# Qwiic_1Wire_to_I2C_Bridge_DS28E17_MILLAB.net
KiCad netlist of a schematic drawn in EAGLE
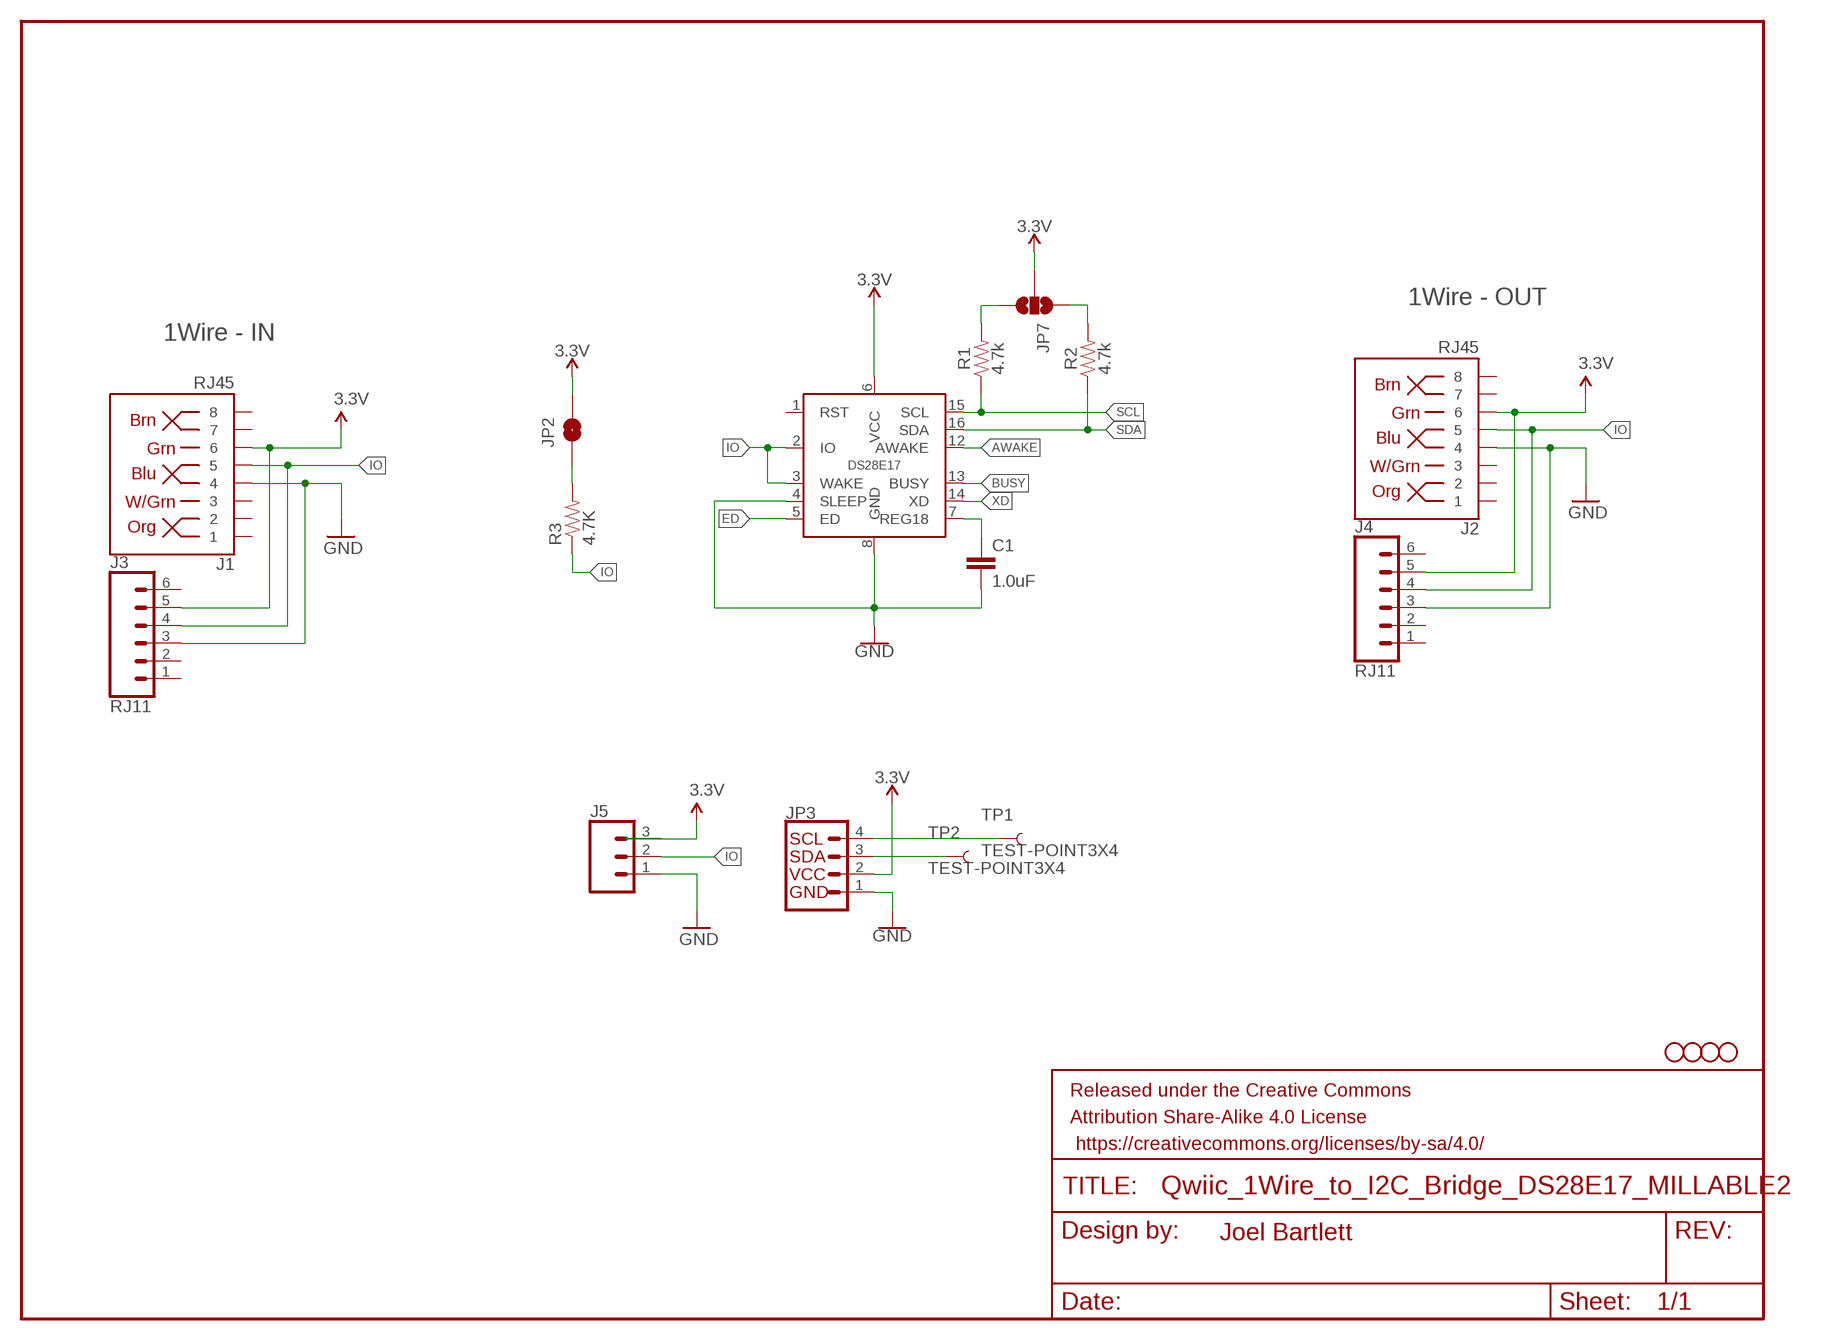
[diagram p0: schematic, sheet 1]

(export (version "E")
  (design (tool "Eeschema 10.0.6"))
  (components
    (comp (ref "C1")
      (value "1.0uF")
      (footprint "eagle-import:0603")
      (libsource (lib "eagle-import") (part "1.0UF-0603-16V-10%"))
    )
    (comp (ref "FRAME1")
      (value "FRAME-LETTER")
      (footprint "eagle-import:CREATIVE_COMMONS")
      (libsource (lib "eagle-import") (part "FRAME-LETTER"))
    )
    (comp (ref "H1")
      (value "STAND-OFF")
      (footprint "eagle-import:STAND-OFF")
      (libsource (lib "eagle-import") (part "STAND-OFF"))
    )
    (comp (ref "H2")
      (value "STAND-OFF")
      (footprint "eagle-import:STAND-OFF")
      (libsource (lib "eagle-import") (part "STAND-OFF"))
    )
    (comp (ref "H3")
      (value "STAND-OFF")
      (footprint "eagle-import:STAND-OFF")
      (libsource (lib "eagle-import") (part "STAND-OFF"))
    )
    (comp (ref "H4")
      (value "STAND-OFF")
      (footprint "eagle-import:STAND-OFF")
      (libsource (lib "eagle-import") (part "STAND-OFF"))
    )
    (comp (ref "J1")
      (value "RJ45")
      (footprint "eagle-import:RJ45-8")
      (libsource (lib "eagle-import") (part "RJ45-8"))
    )
    (comp (ref "J2")
      (value "RJ45")
      (footprint "eagle-import:RJ45-8")
      (libsource (lib "eagle-import") (part "RJ45-8"))
    )
    (comp (ref "J3")
      (value "RJ11")
      (footprint "eagle-import:RJ11-6")
      (libsource (lib "eagle-import") (part "RJ11-6"))
    )
    (comp (ref "J4")
      (value "RJ11")
      (footprint "eagle-import:RJ11-6")
      (libsource (lib "eagle-import") (part "RJ11-6"))
    )
    (comp (ref "J5")
      (value "CONN_03")
      (footprint "eagle-import:1X03")
      (libsource (lib "eagle-import") (part "CONN_03"))
    )
    (comp (ref "JP2")
      (value "JUMPER-SMT_2_NO_NO-SILK")
      (footprint "eagle-import:SMT-JUMPER_2_NO_NO-SILK")
      (libsource (lib "eagle-import") (part "JUMPER-SMT_2_NO_NO-SILK"))
    )
    (comp (ref "JP3")
      (value "I2C_STANDARDJS-1MM")
      (footprint "eagle-import:1X04_1MM_RA")
      (libsource (lib "eagle-import") (part "I2C_STANDARDJS-1MM"))
    )
    (comp (ref "JP7")
      (value "JUMPER-SMT_3_NO_NO-SILK")
      (footprint "eagle-import:SMT-JUMPER_3_NO_NO-SILK")
      (libsource (lib "eagle-import") (part "JUMPER-SMT_3_NO_NO-SILK"))
    )
    (comp (ref "R1")
      (value "4.7k")
      (footprint "eagle-import:0603")
      (libsource (lib "eagle-import") (part "4.7KOHM-0603-1/10W-1%"))
    )
    (comp (ref "R2")
      (value "4.7k")
      (footprint "eagle-import:0603")
      (libsource (lib "eagle-import") (part "4.7KOHM-0603-1/10W-1%"))
    )
    (comp (ref "R3")
      (value "4.7K")
      (footprint "eagle-import:0603-RES")
      (libsource (lib "eagle-import") (part "4.7KOHM-1/10W-1%(0603)"))
    )
    (comp (ref "TP1")
      (value "TEST-POINT3X4")
      (footprint "eagle-import:PAD.03X.04")
      (libsource (lib "eagle-import") (part "TEST-POINT3X4"))
    )
    (comp (ref "TP2")
      (value "TEST-POINT3X4")
      (footprint "eagle-import:PAD.03X.04")
      (libsource (lib "eagle-import") (part "TEST-POINT3X4"))
    )
    (comp (ref "U$1")
      (value "DS28E17")
      (footprint "eagle-import:TQFN-16")
      (libsource (lib "eagle-import") (part "DS28E17"))
    )
  )
  (nets
    (net (code "1") (name "3.3V") (class "Default")
      (node (ref "J1") (pin "6") (pinfunction "6_6") (pintype "bidirectional"))
      (node (ref "J2") (pin "6") (pinfunction "6_6") (pintype "bidirectional"))
      (node (ref "J3") (pin "5") (pinfunction "5_5") (pintype "passive"))
      (node (ref "J4") (pin "5") (pinfunction "5_5") (pintype "passive"))
      (node (ref "J5") (pin "3") (pinfunction "3_3") (pintype "passive"))
      (node (ref "JP2") (pin "2") (pinfunction "2_2") (pintype "passive"))
      (node (ref "JP3") (pin "2") (pinfunction "VCC_2") (pintype "power_in"))
      (node (ref "JP7") (pin "2") (pinfunction "2_2") (pintype "passive"))
      (node (ref "U$1") (pin "6") (pinfunction "VCC_6") (pintype "power_in"))
    )
    (net (code "2") (name "AWAKE") (class "Default")
      (node (ref "U$1") (pin "12") (pinfunction "AWAKE_12") (pintype "bidirectional"))
    )
    (net (code "3") (name "BUSY") (class "Default")
      (node (ref "U$1") (pin "13") (pinfunction "BUSY_13") (pintype "bidirectional"))
    )
    (net (code "4") (name "ED") (class "Default")
      (node (ref "U$1") (pin "5") (pinfunction "ED_5") (pintype "bidirectional"))
    )
    (net (code "5") (name "GND") (class "Default")
      (node (ref "C1") (pin "2") (pinfunction "2_2") (pintype "passive"))
      (node (ref "J1") (pin "4") (pinfunction "4_4") (pintype "bidirectional"))
      (node (ref "J2") (pin "4") (pinfunction "4_4") (pintype "bidirectional"))
      (node (ref "J3") (pin "3") (pinfunction "3_3") (pintype "passive"))
      (node (ref "J4") (pin "3") (pinfunction "3_3") (pintype "passive"))
      (node (ref "J5") (pin "1") (pinfunction "1_1") (pintype "passive"))
      (node (ref "JP3") (pin "1") (pinfunction "GND_1") (pintype "power_in"))
      (node (ref "U$1") (pin "4") (pinfunction "SLEEP_4") (pintype "bidirectional"))
      (node (ref "U$1") (pin "8") (pinfunction "GND_8") (pintype "power_in"))
    )
    (net (code "6") (name "IO") (class "Default")
      (node (ref "J1") (pin "5") (pinfunction "5_5") (pintype "bidirectional"))
      (node (ref "J2") (pin "5") (pinfunction "5_5") (pintype "bidirectional"))
      (node (ref "J3") (pin "4") (pinfunction "4_4") (pintype "passive"))
      (node (ref "J4") (pin "4") (pinfunction "4_4") (pintype "passive"))
      (node (ref "J5") (pin "2") (pinfunction "2_2") (pintype "passive"))
      (node (ref "R3") (pin "1") (pinfunction "1_1") (pintype "passive"))
      (node (ref "U$1") (pin "2") (pinfunction "IO_2") (pintype "bidirectional"))
      (node (ref "U$1") (pin "3") (pinfunction "WAKE_3") (pintype "bidirectional"))
    )
    (net (code "7") (name "Net-(JP2-Pad1)") (class "Default")
      (node (ref "JP2") (pin "1") (pinfunction "1_1") (pintype "passive"))
      (node (ref "R3") (pin "2") (pinfunction "2_2") (pintype "passive"))
    )
    (net (code "8") (name "Net-(JP3-SCL)") (class "Default")
      (node (ref "JP3") (pin "4") (pinfunction "SCL_4") (pintype "passive"))
      (node (ref "TP1") (pin "P$1") (pinfunction "1_P$1") (pintype "bidirectional"))
    )
    (net (code "9") (name "Net-(JP3-SDA)") (class "Default")
      (node (ref "JP3") (pin "3") (pinfunction "SDA_3") (pintype "passive"))
      (node (ref "TP2") (pin "P$1") (pinfunction "1_P$1") (pintype "bidirectional"))
    )
    (net (code "10") (name "Net-(JP7-Pad1)") (class "Default")
      (node (ref "JP7") (pin "1") (pinfunction "1_1") (pintype "passive"))
      (node (ref "R2") (pin "2") (pinfunction "2_2") (pintype "passive"))
    )
    (net (code "11") (name "Net-(JP7-Pad3)") (class "Default")
      (node (ref "JP7") (pin "3") (pinfunction "3_3") (pintype "passive"))
      (node (ref "R1") (pin "2") (pinfunction "2_2") (pintype "passive"))
    )
    (net (code "12") (name "Net-(U$1-REG18)") (class "Default")
      (node (ref "C1") (pin "1") (pinfunction "1_1") (pintype "passive"))
      (node (ref "U$1") (pin "7") (pinfunction "REG18_7") (pintype "bidirectional"))
    )
    (net (code "13") (name "SCL") (class "Default")
      (node (ref "R1") (pin "1") (pinfunction "1_1") (pintype "passive"))
      (node (ref "U$1") (pin "15") (pinfunction "SCL_15") (pintype "bidirectional"))
    )
    (net (code "14") (name "SDA") (class "Default")
      (node (ref "R2") (pin "1") (pinfunction "1_1") (pintype "passive"))
      (node (ref "U$1") (pin "16") (pinfunction "SDA_16") (pintype "bidirectional"))
    )
    (net (code "15") (name "XD") (class "Default")
      (node (ref "U$1") (pin "14") (pinfunction "XD_14") (pintype "bidirectional"))
    )
    (net (code "16") (name "unconnected-(J1-Pad1)") (class "Default")
      (node (ref "J1") (pin "1") (pinfunction "1_1") (pintype "bidirectional"))
    )
    (net (code "17") (name "unconnected-(J1-Pad2)") (class "Default")
      (node (ref "J1") (pin "2") (pinfunction "2_2") (pintype "bidirectional"))
    )
    (net (code "18") (name "unconnected-(J1-Pad3)") (class "Default")
      (node (ref "J1") (pin "3") (pinfunction "3_3") (pintype "bidirectional"))
    )
    (net (code "19") (name "unconnected-(J1-Pad7)") (class "Default")
      (node (ref "J1") (pin "7") (pinfunction "7_7") (pintype "bidirectional"))
    )
    (net (code "20") (name "unconnected-(J1-Pad8)") (class "Default")
      (node (ref "J1") (pin "8") (pinfunction "8_8") (pintype "bidirectional"))
    )
    (net (code "21") (name "unconnected-(J2-Pad1)") (class "Default")
      (node (ref "J2") (pin "1") (pinfunction "1_1") (pintype "bidirectional"))
    )
    (net (code "22") (name "unconnected-(J2-Pad2)") (class "Default")
      (node (ref "J2") (pin "2") (pinfunction "2_2") (pintype "bidirectional"))
    )
    (net (code "23") (name "unconnected-(J2-Pad3)") (class "Default")
      (node (ref "J2") (pin "3") (pinfunction "3_3") (pintype "bidirectional"))
    )
    (net (code "24") (name "unconnected-(J2-Pad7)") (class "Default")
      (node (ref "J2") (pin "7") (pinfunction "7_7") (pintype "bidirectional"))
    )
    (net (code "25") (name "unconnected-(J2-Pad8)") (class "Default")
      (node (ref "J2") (pin "8") (pinfunction "8_8") (pintype "bidirectional"))
    )
    (net (code "26") (name "unconnected-(J3-Pad1)") (class "Default")
      (node (ref "J3") (pin "1") (pinfunction "1_1") (pintype "passive"))
    )
    (net (code "27") (name "unconnected-(J3-Pad2)") (class "Default")
      (node (ref "J3") (pin "2") (pinfunction "2_2") (pintype "passive"))
    )
    (net (code "28") (name "unconnected-(J3-Pad6)") (class "Default")
      (node (ref "J3") (pin "6") (pinfunction "6_6") (pintype "passive"))
    )
    (net (code "29") (name "unconnected-(J4-Pad1)") (class "Default")
      (node (ref "J4") (pin "1") (pinfunction "1_1") (pintype "passive"))
    )
    (net (code "30") (name "unconnected-(J4-Pad2)") (class "Default")
      (node (ref "J4") (pin "2") (pinfunction "2_2") (pintype "passive"))
    )
    (net (code "31") (name "unconnected-(J4-Pad6)") (class "Default")
      (node (ref "J4") (pin "6") (pinfunction "6_6") (pintype "passive"))
    )
    (net (code "32") (name "unconnected-(U$1-RST-Pad1)") (class "Default")
      (node (ref "U$1") (pin "1") (pinfunction "RST_1") (pintype "bidirectional"))
    )
  )
)
